# hat_v2.net
KiCad netlist of a schematic drawn in EAGLE
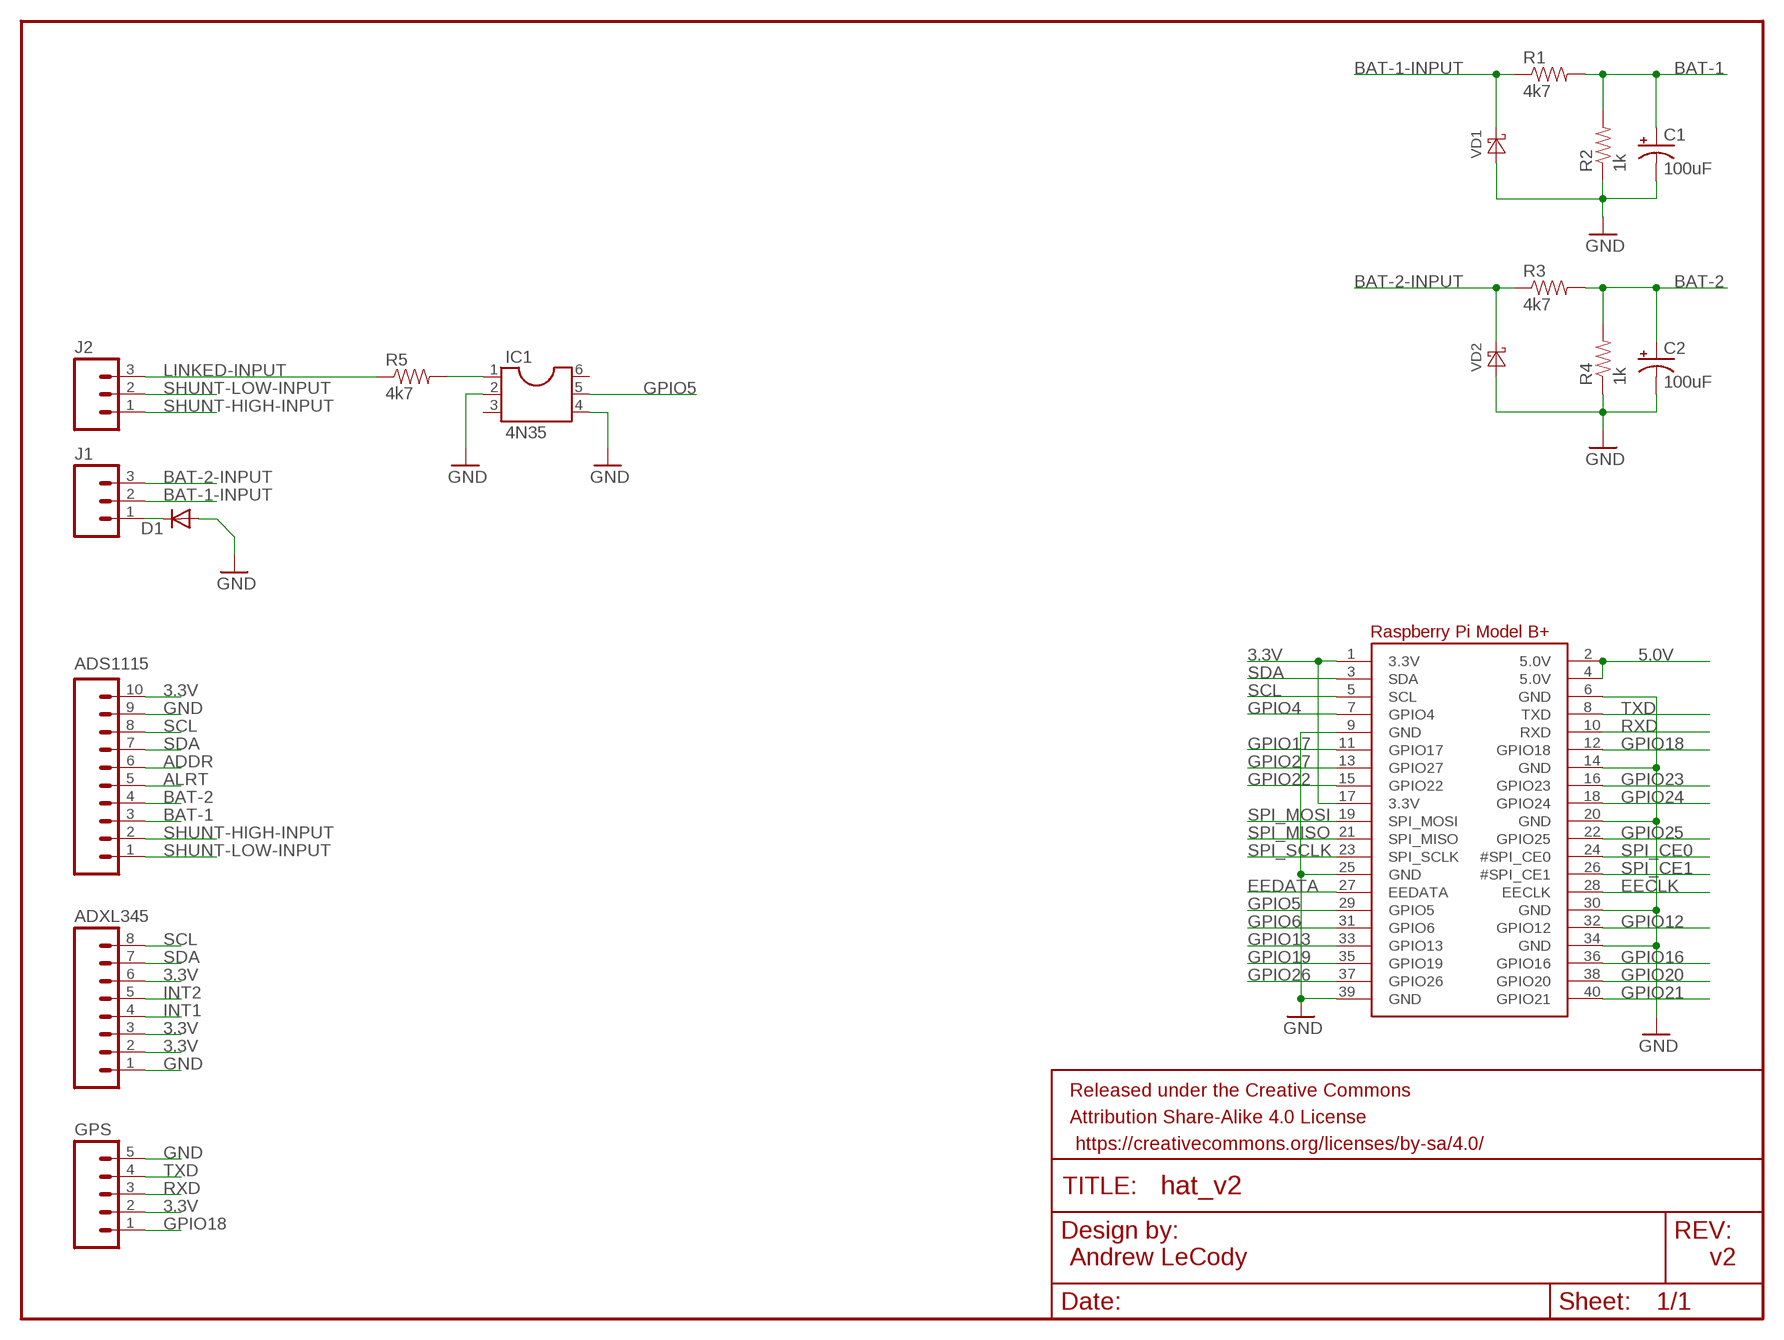
[diagram p0: schematic, sheet 1]

(export (version "E")
  (design (tool "Eeschema 10.0.6"))
  (components
    (comp (ref "ADS1115")
      (value "M10SILK_FEMALE_PTH")
      (footprint "eagle-import:1X10")
      (libsource (lib "eagle-import") (part "M10SILK_FEMALE_PTH"))
    )
    (comp (ref "ADXL345")
      (value "M08SILK_FEMALE_PTH")
      (footprint "eagle-import:1X08")
      (libsource (lib "eagle-import") (part "M08SILK_FEMALE_PTH"))
    )
    (comp (ref "C1")
      (value "100uF")
      (footprint "eagle-import:CPOL-RADIAL-100UF-25V")
      (libsource (lib "eagle-import") (part "CAP_POLPTH1"))
    )
    (comp (ref "C2")
      (value "100uF")
      (footprint "eagle-import:CPOL-RADIAL-100UF-25V")
      (libsource (lib "eagle-import") (part "CAP_POLPTH1"))
    )
    (comp (ref "D1")
      (value "DIODE-DO41-10")
      (footprint "eagle-import:DO41-10")
      (libsource (lib "eagle-import") (part "DIODE-DO41-10"))
    )
    (comp (ref "FRAME1")
      (value "FRAME-LETTER")
      (footprint "eagle-import:CREATIVE_COMMONS")
      (libsource (lib "eagle-import") (part "FRAME-LETTER"))
    )
    (comp (ref "GPS")
      (value "M05PTH")
      (footprint "eagle-import:1X05")
      (libsource (lib "eagle-import") (part "M05PTH"))
    )
    (comp (ref "IC1")
      (value "4N35")
      (footprint "eagle-import:DIL06")
      (libsource (lib "eagle-import") (part "DIL6"))
    )
    (comp (ref "J1")
      (value "M03-SCREW-5MM")
      (footprint "eagle-import:SCREWTERMINAL-5MM-3")
      (libsource (lib "eagle-import") (part "M03-SCREW-5MM"))
    )
    (comp (ref "J2")
      (value "M03-SCREW-5MM")
      (footprint "eagle-import:SCREWTERMINAL-5MM-3")
      (libsource (lib "eagle-import") (part "M03-SCREW-5MM"))
    )
    (comp (ref "R1")
      (value "4k7")
      (footprint "eagle-import:AXIAL-0.3")
      (libsource (lib "eagle-import") (part "RESISTORAXIAL-0.3"))
    )
    (comp (ref "R2")
      (value "1k")
      (footprint "eagle-import:AXIAL-0.3")
      (libsource (lib "eagle-import") (part "RESISTORAXIAL-0.3"))
    )
    (comp (ref "R3")
      (value "4k7")
      (footprint "eagle-import:AXIAL-0.3")
      (libsource (lib "eagle-import") (part "RESISTORAXIAL-0.3"))
    )
    (comp (ref "R4")
      (value "1k")
      (footprint "eagle-import:AXIAL-0.3")
      (libsource (lib "eagle-import") (part "RESISTORAXIAL-0.3"))
    )
    (comp (ref "R5")
      (value "4k7")
      (footprint "eagle-import:AXIAL-0.3")
      (libsource (lib "eagle-import") (part "RESISTORAXIAL-0.3"))
    )
    (comp (ref "RPI1")
      (value "RASPBERRYPI_BPLUS_HATNOSLOTS")
      (footprint "eagle-import:PI_HAT_NOSLOTS")
      (libsource (lib "eagle-import") (part "RASPBERRYPI_BPLUS_HATNOSLOTS"))
    )
    (comp (ref "VD1")
      (value "DIODE-SCHOTTKY-DO201AD")
      (footprint "eagle-import:DO201AD")
      (libsource (lib "eagle-import") (part "DIODE-SCHOTTKY-DO201AD"))
    )
    (comp (ref "VD2")
      (value "DIODE-SCHOTTKY-DO201AD")
      (footprint "eagle-import:DO201AD")
      (libsource (lib "eagle-import") (part "DIODE-SCHOTTKY-DO201AD"))
    )
  )
  (nets
    (net (code "1") (name "/3.3V") (class "Default")
      (node (ref "ADS1115") (pin "10") (pinfunction "10_10") (pintype "passive"))
      (node (ref "ADXL345") (pin "2") (pinfunction "2_2") (pintype "passive"))
      (node (ref "ADXL345") (pin "3") (pinfunction "3_3") (pintype "passive"))
      (node (ref "ADXL345") (pin "6") (pinfunction "6_6") (pintype "passive"))
      (node (ref "GPS") (pin "2") (pinfunction "2_2") (pintype "passive"))
      (node (ref "RPI1") (pin "1") (pinfunction "3.3V_1") (pintype "power_in"))
      (node (ref "RPI1") (pin "17") (pinfunction "3.3V_17") (pintype "power_in"))
    )
    (net (code "2") (name "/5.0V") (class "Default")
      (node (ref "RPI1") (pin "2") (pinfunction "5.0V_2") (pintype "power_in"))
      (node (ref "RPI1") (pin "4") (pinfunction "5.0V_4") (pintype "power_in"))
    )
    (net (code "3") (name "/ADDR") (class "Default")
      (node (ref "ADS1115") (pin "6") (pinfunction "6_6") (pintype "passive"))
    )
    (net (code "4") (name "/ALRT") (class "Default")
      (node (ref "ADS1115") (pin "5") (pinfunction "5_5") (pintype "passive"))
    )
    (net (code "5") (name "/BAT-1") (class "Default")
      (node (ref "ADS1115") (pin "3") (pinfunction "3_3") (pintype "passive"))
      (node (ref "C1") (pin "1") (pinfunction "+_1") (pintype "passive"))
      (node (ref "R1") (pin "P$2") (pinfunction "2_P$2") (pintype "passive"))
      (node (ref "R2") (pin "P$2") (pinfunction "2_P$2") (pintype "passive"))
    )
    (net (code "6") (name "/BAT-1-INPUT") (class "Default")
      (node (ref "J1") (pin "2") (pinfunction "2_2") (pintype "passive"))
      (node (ref "R1") (pin "P$1") (pinfunction "1_P$1") (pintype "passive"))
      (node (ref "VD1") (pin "C") (pinfunction "C_C") (pintype "passive"))
    )
    (net (code "7") (name "/BAT-2") (class "Default")
      (node (ref "ADS1115") (pin "4") (pinfunction "4_4") (pintype "passive"))
      (node (ref "C2") (pin "1") (pinfunction "+_1") (pintype "passive"))
      (node (ref "R3") (pin "P$2") (pinfunction "2_P$2") (pintype "passive"))
      (node (ref "R4") (pin "P$2") (pinfunction "2_P$2") (pintype "passive"))
    )
    (net (code "8") (name "/BAT-2-INPUT") (class "Default")
      (node (ref "J1") (pin "3") (pinfunction "3_3") (pintype "passive"))
      (node (ref "R3") (pin "P$1") (pinfunction "1_P$1") (pintype "passive"))
      (node (ref "VD2") (pin "C") (pinfunction "C_C") (pintype "passive"))
    )
    (net (code "9") (name "/EECLK") (class "Default")
      (node (ref "RPI1") (pin "28") (pinfunction "EECLK_28") (pintype "power_in"))
    )
    (net (code "10") (name "/EEDATA") (class "Default")
      (node (ref "RPI1") (pin "27") (pinfunction "EEDATA_27") (pintype "bidirectional"))
    )
    (net (code "11") (name "/GPIO4") (class "Default")
      (node (ref "RPI1") (pin "7") (pinfunction "GPIO4_7") (pintype "bidirectional"))
    )
    (net (code "12") (name "/GPIO5") (class "Default")
      (node (ref "IC1") (pin "5") (pinfunction "5_5") (pintype "passive"))
      (node (ref "RPI1") (pin "29") (pinfunction "GPIO5_29") (pintype "bidirectional"))
    )
    (net (code "13") (name "/GPIO6") (class "Default")
      (node (ref "RPI1") (pin "31") (pinfunction "GPIO6_31") (pintype "power_in"))
    )
    (net (code "14") (name "/GPIO12") (class "Default")
      (node (ref "RPI1") (pin "32") (pinfunction "GPIO12_32") (pintype "bidirectional"))
    )
    (net (code "15") (name "/GPIO13") (class "Default")
      (node (ref "RPI1") (pin "33") (pinfunction "GPIO13_33") (pintype "bidirectional"))
    )
    (net (code "16") (name "/GPIO16") (class "Default")
      (node (ref "RPI1") (pin "36") (pinfunction "GPIO16_36") (pintype "power_in"))
    )
    (net (code "17") (name "/GPIO17") (class "Default")
      (node (ref "RPI1") (pin "11") (pinfunction "GPIO17_11") (pintype "bidirectional"))
    )
    (net (code "18") (name "/GPIO18") (class "Default")
      (node (ref "GPS") (pin "1") (pinfunction "1_1") (pintype "passive"))
      (node (ref "RPI1") (pin "12") (pinfunction "GPIO18_12") (pintype "bidirectional"))
    )
    (net (code "19") (name "/GPIO19") (class "Default")
      (node (ref "RPI1") (pin "35") (pinfunction "GPIO19_35") (pintype "bidirectional"))
    )
    (net (code "20") (name "/GPIO20") (class "Default")
      (node (ref "RPI1") (pin "38") (pinfunction "GPIO20_38") (pintype "bidirectional"))
    )
    (net (code "21") (name "/GPIO21") (class "Default")
      (node (ref "RPI1") (pin "40") (pinfunction "GPIO21_40") (pintype "bidirectional"))
    )
    (net (code "22") (name "/GPIO22") (class "Default")
      (node (ref "RPI1") (pin "15") (pinfunction "GPIO22_15") (pintype "bidirectional"))
    )
    (net (code "23") (name "/GPIO23") (class "Default")
      (node (ref "RPI1") (pin "16") (pinfunction "GPIO23_16") (pintype "bidirectional"))
    )
    (net (code "24") (name "/GPIO24") (class "Default")
      (node (ref "RPI1") (pin "18") (pinfunction "GPIO24_18") (pintype "bidirectional"))
    )
    (net (code "25") (name "/GPIO25") (class "Default")
      (node (ref "RPI1") (pin "22") (pinfunction "GPIO25_22") (pintype "bidirectional"))
    )
    (net (code "26") (name "/GPIO26") (class "Default")
      (node (ref "RPI1") (pin "37") (pinfunction "GPIO26_37") (pintype "bidirectional"))
    )
    (net (code "27") (name "/GPIO27") (class "Default")
      (node (ref "RPI1") (pin "13") (pinfunction "GPIO27_13") (pintype "bidirectional"))
    )
    (net (code "28") (name "/INT1") (class "Default")
      (node (ref "ADXL345") (pin "4") (pinfunction "4_4") (pintype "passive"))
    )
    (net (code "29") (name "/INT2") (class "Default")
      (node (ref "ADXL345") (pin "5") (pinfunction "5_5") (pintype "passive"))
    )
    (net (code "30") (name "/LINKED-INPUT") (class "Default")
      (node (ref "J2") (pin "3") (pinfunction "3_3") (pintype "passive"))
      (node (ref "R5") (pin "P$1") (pinfunction "1_P$1") (pintype "passive"))
    )
    (net (code "31") (name "/RXD") (class "Default")
      (node (ref "GPS") (pin "3") (pinfunction "3_3") (pintype "passive"))
      (node (ref "RPI1") (pin "10") (pinfunction "RXD_10") (pintype "bidirectional"))
    )
    (net (code "32") (name "/SCL") (class "Default")
      (node (ref "ADS1115") (pin "8") (pinfunction "8_8") (pintype "passive"))
      (node (ref "ADXL345") (pin "8") (pinfunction "8_8") (pintype "passive"))
      (node (ref "RPI1") (pin "5") (pinfunction "SCL_5") (pintype "bidirectional"))
    )
    (net (code "33") (name "/SDA") (class "Default")
      (node (ref "ADS1115") (pin "7") (pinfunction "7_7") (pintype "passive"))
      (node (ref "ADXL345") (pin "7") (pinfunction "7_7") (pintype "passive"))
      (node (ref "RPI1") (pin "3") (pinfunction "SDA_3") (pintype "bidirectional"))
    )
    (net (code "34") (name "/SHUNT-HIGH-INPUT") (class "Default")
      (node (ref "ADS1115") (pin "2") (pinfunction "2_2") (pintype "passive"))
      (node (ref "J2") (pin "1") (pinfunction "1_1") (pintype "passive"))
    )
    (net (code "35") (name "/SHUNT-LOW-INPUT") (class "Default")
      (node (ref "ADS1115") (pin "1") (pinfunction "1_1") (pintype "passive"))
      (node (ref "J2") (pin "2") (pinfunction "2_2") (pintype "passive"))
    )
    (net (code "36") (name "/SPI_CE0") (class "Default")
      (node (ref "RPI1") (pin "24") (pinfunction "#SPI_CE0_24") (pintype "bidirectional"))
    )
    (net (code "37") (name "/SPI_CE1") (class "Default")
      (node (ref "RPI1") (pin "26") (pinfunction "#SPI_CE1_26") (pintype "bidirectional"))
    )
    (net (code "38") (name "/SPI_MISO") (class "Default")
      (node (ref "RPI1") (pin "21") (pinfunction "SPI_MISO_21") (pintype "bidirectional"))
    )
    (net (code "39") (name "/SPI_MOSI") (class "Default")
      (node (ref "RPI1") (pin "19") (pinfunction "SPI_MOSI_19") (pintype "bidirectional"))
    )
    (net (code "40") (name "/SPI_SCLK") (class "Default")
      (node (ref "RPI1") (pin "23") (pinfunction "SPI_SCLK_23") (pintype "bidirectional"))
    )
    (net (code "41") (name "/TXD") (class "Default")
      (node (ref "GPS") (pin "4") (pinfunction "4_4") (pintype "passive"))
      (node (ref "RPI1") (pin "8") (pinfunction "TXD_8") (pintype "output"))
    )
    (net (code "42") (name "GND") (class "Default")
      (node (ref "ADS1115") (pin "9") (pinfunction "9_9") (pintype "passive"))
      (node (ref "ADXL345") (pin "1") (pinfunction "1_1") (pintype "passive"))
      (node (ref "C1") (pin "2") (pinfunction "-_2") (pintype "passive"))
      (node (ref "C2") (pin "2") (pinfunction "-_2") (pintype "passive"))
      (node (ref "D1") (pin "A") (pinfunction "A_A") (pintype "passive"))
      (node (ref "GPS") (pin "5") (pinfunction "5_5") (pintype "passive"))
      (node (ref "IC1") (pin "2") (pinfunction "2_2") (pintype "passive"))
      (node (ref "IC1") (pin "4") (pinfunction "4_4") (pintype "passive"))
      (node (ref "R2") (pin "P$1") (pinfunction "1_P$1") (pintype "passive"))
      (node (ref "R4") (pin "P$1") (pinfunction "1_P$1") (pintype "passive"))
      (node (ref "RPI1") (pin "14") (pinfunction "GND_14") (pintype "power_in"))
      (node (ref "RPI1") (pin "20") (pinfunction "GND_20") (pintype "power_in"))
      (node (ref "RPI1") (pin "25") (pinfunction "GND_25") (pintype "power_in"))
      (node (ref "RPI1") (pin "30") (pinfunction "GND_30") (pintype "bidirectional"))
      (node (ref "RPI1") (pin "34") (pinfunction "GND_34") (pintype "bidirectional"))
      (node (ref "RPI1") (pin "39") (pinfunction "GND_39") (pintype "power_in"))
      (node (ref "RPI1") (pin "6") (pinfunction "GND_6") (pintype "power_in"))
      (node (ref "RPI1") (pin "9") (pinfunction "GND_9") (pintype "power_in"))
      (node (ref "VD1") (pin "A") (pinfunction "A_A") (pintype "passive"))
      (node (ref "VD2") (pin "A") (pinfunction "A_A") (pintype "passive"))
    )
    (net (code "43") (name "Net-(D1-PadC)") (class "Default")
      (node (ref "D1") (pin "C") (pinfunction "C_C") (pintype "passive"))
      (node (ref "J1") (pin "1") (pinfunction "1_1") (pintype "passive"))
    )
    (net (code "44") (name "Net-(R5-2)") (class "Default")
      (node (ref "IC1") (pin "1") (pinfunction "1_1") (pintype "passive"))
      (node (ref "R5") (pin "P$2") (pinfunction "2_P$2") (pintype "passive"))
    )
    (net (code "45") (name "unconnected-(IC1-Pad3)") (class "Default")
      (node (ref "IC1") (pin "3") (pinfunction "3_3") (pintype "passive"))
    )
    (net (code "46") (name "unconnected-(IC1-Pad6)") (class "Default")
      (node (ref "IC1") (pin "6") (pinfunction "6_6") (pintype "passive"))
    )
  )
)
